# bb-psu-mk-1_0.net
KiCad netlist of a schematic drawn in EAGLE
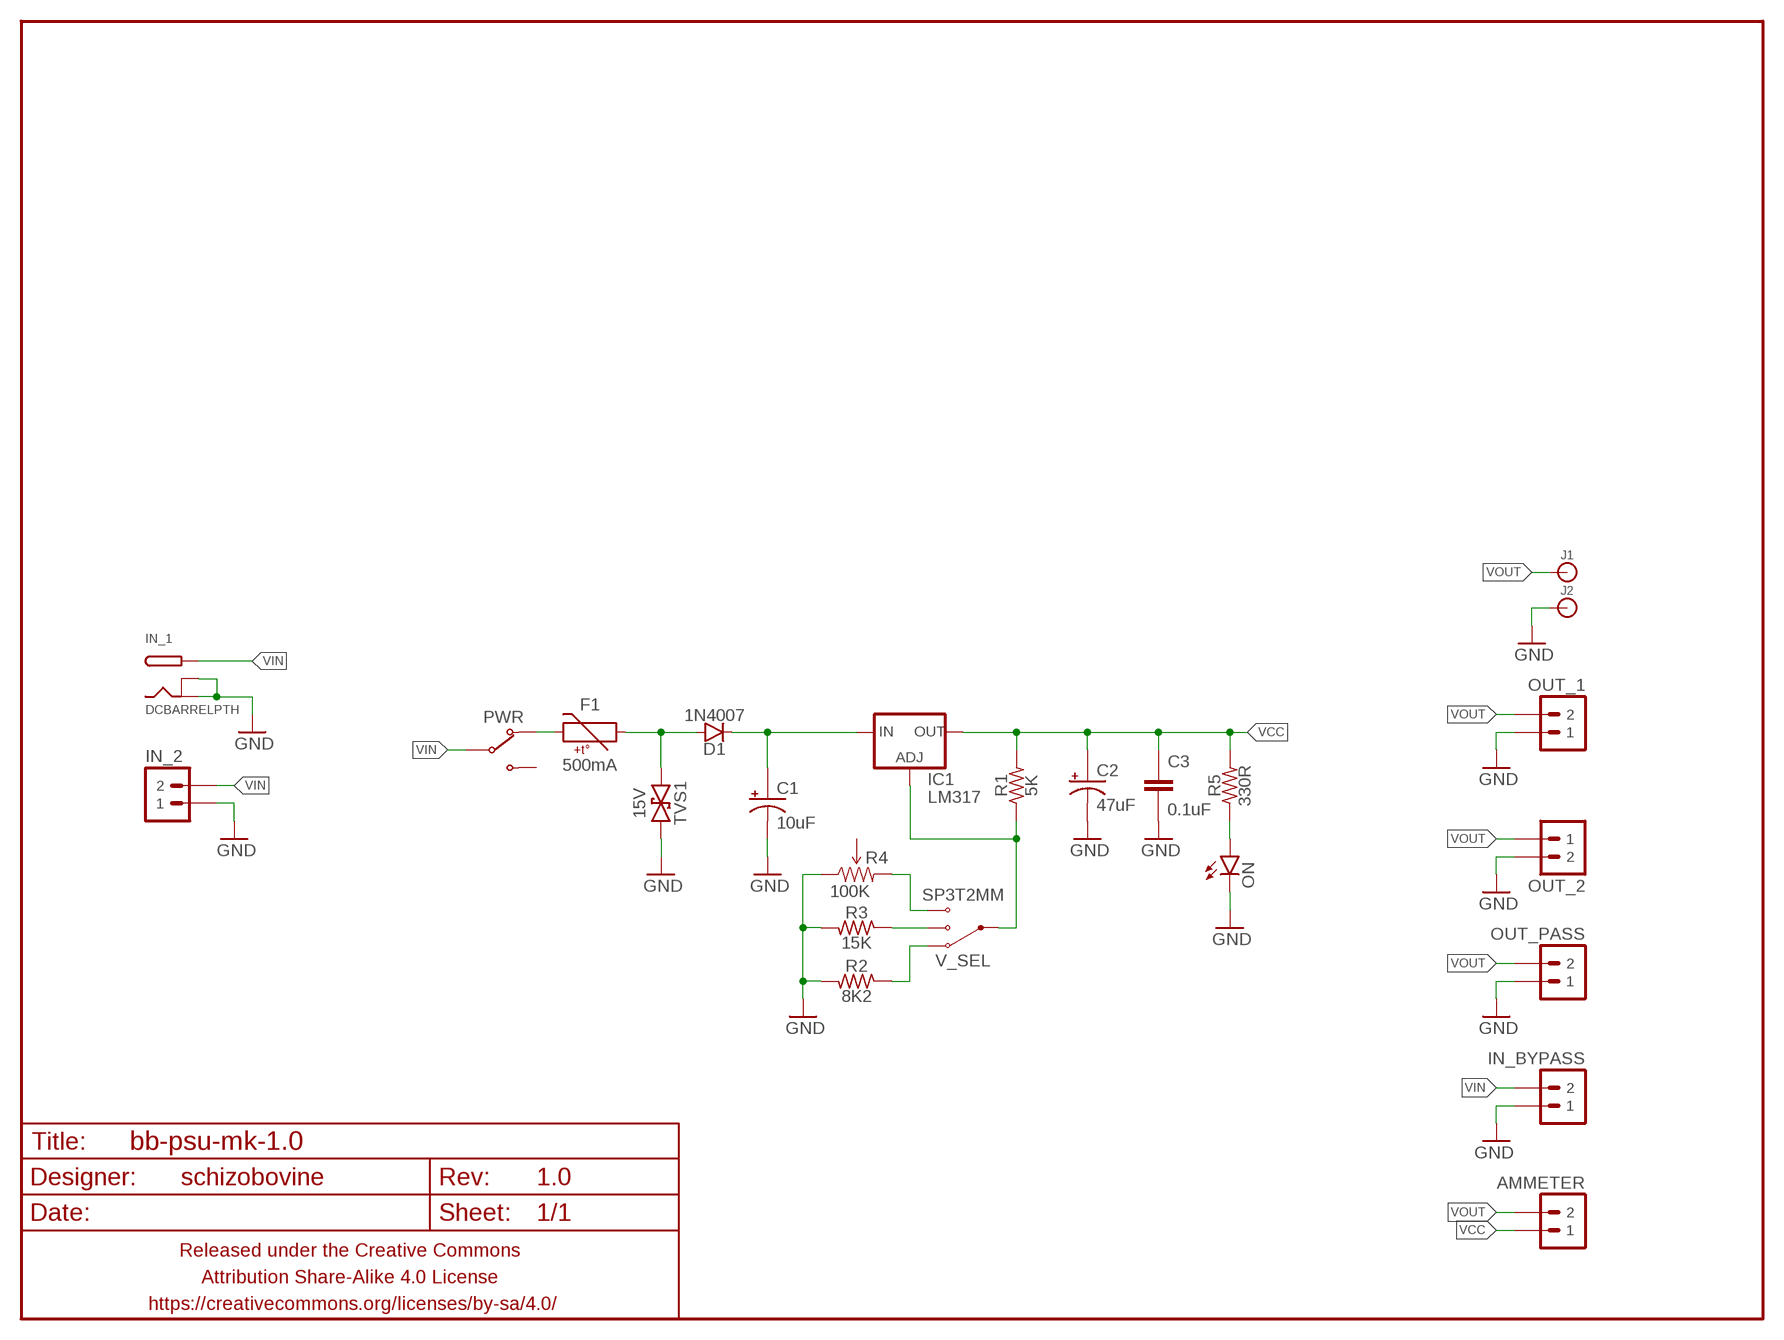
[diagram p0: schematic, sheet 1]

(export (version "E")
  (design (tool "Eeschema 10.0.6"))
  (components
    (comp (ref "AMMETER")
      (value "M02PTH-CENTERED")
      (footprint "eagle-import:1X02-CENTER")
      (libsource (lib "eagle-import") (part "M02PTH-CENTERED"))
    )
    (comp (ref "C1")
      (value "10uF")
      (footprint "eagle-import:E2,5-6")
      (libsource (lib "eagle-import") (part "CAPACITOR-POLARIZEDE2.5-6"))
    )
    (comp (ref "C2")
      (value "47uF")
      (footprint "eagle-import:E2,5-6")
      (libsource (lib "eagle-import") (part "CAPACITOR-POLARIZEDE2.5-6"))
    )
    (comp (ref "C3")
      (value "0.1uF")
      (footprint "eagle-import:C025-024X044")
      (libsource (lib "eagle-import") (part "CAPACITOR-CERAMIC025-024X044"))
    )
    (comp (ref "D1")
      (value "1N4007")
      (footprint "eagle-import:DIODE-10.16MM")
      (libsource (lib "eagle-import") (part "DIODEPTH-10.68MM"))
    )
    (comp (ref "F1")
      (value "500mA")
      (footprint "eagle-import:PTC-PTH-5.08MM")
      (libsource (lib "eagle-import") (part "PTCPTH-5.08MM"))
    )
    (comp (ref "FRAME1")
      (value "FRAME-LETTERNO_PACKAGE")
      (footprint "eagle-import:DUMMY")
      (fields (field (name "DESIGNER") "schizobovine") (field (name "VERSION") "1.0"))
      (libsource (lib "eagle-import") (part "FRAME-LETTERNO_PACKAGE"))
    )
    (comp (ref "IC1")
      (value "LM317")
      (footprint "eagle-import:TO220-THERMPAD")
      (libsource (lib "eagle-import") (part "V_REG_317THERMPAD"))
    )
    (comp (ref "IN_1")
      (value "DCBARRELPTH")
      (footprint "eagle-import:DCJACK_2MM_PTH")
      (libsource (lib "eagle-import") (part "DCBARRELPTH"))
    )
    (comp (ref "IN_2")
      (value "M02PTH-CENTERED-R+")
      (footprint "eagle-import:1X02-CENTER-R+")
      (libsource (lib "eagle-import") (part "M02PTH-CENTERED-R+"))
    )
    (comp (ref "IN_BYPASS")
      (value "M02PTH-CENTERED-R+")
      (footprint "eagle-import:1X02-CENTER-R+")
      (libsource (lib "eagle-import") (part "M02PTH-CENTERED-R+"))
    )
    (comp (ref "J1")
      (value "BANANA_CONNPOAST")
      (footprint "eagle-import:BINDING_POST")
      (libsource (lib "eagle-import") (part "BANANA_CONNPOAST"))
    )
    (comp (ref "J2")
      (value "BANANA_CONNPOAST")
      (footprint "eagle-import:BINDING_POST")
      (libsource (lib "eagle-import") (part "BANANA_CONNPOAST"))
    )
    (comp (ref "ON")
      (value "LED3MM-LESS")
      (footprint "eagle-import:LED3MM-LESSSILK")
      (libsource (lib "eagle-import") (part "LED3MM-LESS"))
    )
    (comp (ref "OUT_1")
      (value "M02PTH-CENTERED-R+")
      (footprint "eagle-import:1X02-CENTER-R+")
      (libsource (lib "eagle-import") (part "M02PTH-CENTERED-R+"))
    )
    (comp (ref "OUT_2")
      (value "M023.5MM")
      (footprint "eagle-import:SCREWTERMINAL-3.5MM-2")
      (libsource (lib "eagle-import") (part "M023.5MM"))
    )
    (comp (ref "OUT_PASS")
      (value "M02PTH-CENTERED-R+")
      (footprint "eagle-import:1X02-CENTER-R+")
      (libsource (lib "eagle-import") (part "M02PTH-CENTERED-R+"))
    )
    (comp (ref "PWR")
      (value "SWITCH-SPDTPTH-RA-2.54MM")
      (footprint "eagle-import:SPDT-RA-2.54MM")
      (libsource (lib "eagle-import") (part "SWITCH-SPDTPTH-RA-2.54MM"))
    )
    (comp (ref "R1")
      (value "5K")
      (footprint "eagle-import:RESISTOR-AXIAL-PTH-6.35MM")
      (libsource (lib "eagle-import") (part "RESISTORPTH-AXIAL-6.35MM"))
    )
    (comp (ref "R2")
      (value "8K2")
      (footprint "eagle-import:RESISTOR-AXIAL-PTH-6.35MM")
      (libsource (lib "eagle-import") (part "RESISTORPTH-AXIAL-6.35MM"))
    )
    (comp (ref "R3")
      (value "15K")
      (footprint "eagle-import:RESISTOR-AXIAL-PTH-6.35MM")
      (libsource (lib "eagle-import") (part "RESISTORPTH-AXIAL-6.35MM"))
    )
    (comp (ref "R4")
      (value "100K")
      (footprint "eagle-import:3386U")
      (libsource (lib "eagle-import") (part "TRIMPOT-PTH-KNOB"))
    )
    (comp (ref "R5")
      (value "330R")
      (footprint "eagle-import:RESISTOR-AXIAL-PTH-6.35MM")
      (libsource (lib "eagle-import") (part "RESISTORPTH-AXIAL-6.35MM"))
    )
    (comp (ref "TVS1")
      (value "15V")
      (footprint "eagle-import:DO-41-TVS-BI-10.16MM")
      (libsource (lib "eagle-import") (part "TVSDO-41-10.16MM"))
    )
    (comp (ref "V_SEL")
      (value "SP3T2MM")
      (footprint "eagle-import:SP3T-2MM")
      (libsource (lib "eagle-import") (part "SP3T2MM"))
    )
  )
  (nets
    (net (code "1") (name "GND") (class "Default")
      (node (ref "C1") (pin "-") (pinfunction "-_-") (pintype "passive"))
      (node (ref "C2") (pin "-") (pinfunction "-_-") (pintype "passive"))
      (node (ref "C3") (pin "2") (pinfunction "2_2") (pintype "passive"))
      (node (ref "IN_1") (pin "BRK") (pinfunction "BRK_BRK") (pintype "bidirectional"))
      (node (ref "IN_1") (pin "GND") (pinfunction "GND_GND") (pintype "bidirectional"))
      (node (ref "IN_2") (pin "1") (pinfunction "1_1") (pintype "passive"))
      (node (ref "IN_BYPASS") (pin "1") (pinfunction "1_1") (pintype "passive"))
      (node (ref "J2") (pin "P$1") (pinfunction "1_P$1") (pintype "passive"))
      (node (ref "ON") (pin "K") (pinfunction "C_K") (pintype "passive"))
      (node (ref "OUT_1") (pin "1") (pinfunction "1_1") (pintype "passive"))
      (node (ref "OUT_2") (pin "2") (pinfunction "2_2") (pintype "passive"))
      (node (ref "OUT_PASS") (pin "1") (pinfunction "1_1") (pintype "passive"))
      (node (ref "R2") (pin "P$2") (pinfunction "2_P$2") (pintype "passive"))
      (node (ref "R3") (pin "P$2") (pinfunction "2_P$2") (pintype "passive"))
      (node (ref "R4") (pin "1") (pinfunction "CCW_1") (pintype "passive"))
      (node (ref "TVS1") (pin "P$2") (pinfunction "2_P$2") (pintype "passive"))
    )
    (net (code "2") (name "Net-(F1-1)") (class "Default")
      (node (ref "D1") (pin "A") (pinfunction "A_A") (pintype "passive"))
      (node (ref "F1") (pin "P$1") (pinfunction "1_P$1") (pintype "passive"))
      (node (ref "TVS1") (pin "P$1") (pinfunction "1_P$1") (pintype "passive"))
    )
    (net (code "3") (name "Net-(F1-2)") (class "Default")
      (node (ref "F1") (pin "P$2") (pinfunction "2_P$2") (pintype "passive"))
      (node (ref "PWR") (pin "1") (pinfunction "NC_1") (pintype "passive"))
    )
    (net (code "4") (name "Net-(IC1-ADJ)") (class "Default")
      (node (ref "IC1") (pin "1") (pinfunction "ADJ_1") (pintype "input"))
      (node (ref "R1") (pin "P$1") (pinfunction "1_P$1") (pintype "passive"))
      (node (ref "V_SEL") (pin "P$1") (pinfunction "COM_P$1") (pintype "bidirectional"))
    )
    (net (code "5") (name "Net-(IC1-IN)") (class "Default")
      (node (ref "C1") (pin "+") (pinfunction "+_+") (pintype "passive"))
      (node (ref "D1") (pin "C") (pinfunction "C_C") (pintype "passive"))
      (node (ref "IC1") (pin "3") (pinfunction "IN_3") (pintype "input"))
    )
    (net (code "6") (name "Net-(R2-1)") (class "Default")
      (node (ref "R2") (pin "P$1") (pinfunction "1_P$1") (pintype "passive"))
      (node (ref "V_SEL") (pin "P$2") (pinfunction "A_P$2") (pintype "bidirectional"))
    )
    (net (code "7") (name "Net-(R3-1)") (class "Default")
      (node (ref "R3") (pin "P$1") (pinfunction "1_P$1") (pintype "passive"))
      (node (ref "V_SEL") (pin "P$3") (pinfunction "B_P$3") (pintype "bidirectional"))
    )
    (net (code "8") (name "Net-(R4-CW)") (class "Default")
      (node (ref "R4") (pin "3") (pinfunction "CW_3") (pintype "passive"))
      (node (ref "V_SEL") (pin "P$4") (pinfunction "C_P$4") (pintype "bidirectional"))
    )
    (net (code "9") (name "Net-(R5-1)") (class "Default")
      (node (ref "ON") (pin "A") (pinfunction "A_A") (pintype "passive"))
      (node (ref "R5") (pin "P$1") (pinfunction "1_P$1") (pintype "passive"))
    )
    (net (code "10") (name "VCC") (class "Default")
      (node (ref "AMMETER") (pin "1") (pinfunction "1_1") (pintype "passive"))
      (node (ref "C2") (pin "+") (pinfunction "+_+") (pintype "passive"))
      (node (ref "C3") (pin "1") (pinfunction "1_1") (pintype "passive"))
      (node (ref "IC1") (pin "2@1") (pinfunction "OUT_2@1") (pintype "output"))
      (node (ref "IC1") (pin "2@2") (pinfunction "OUT_2@2") (pintype "output"))
      (node (ref "R1") (pin "P$2") (pinfunction "2_P$2") (pintype "passive"))
      (node (ref "R5") (pin "P$2") (pinfunction "2_P$2") (pintype "passive"))
    )
    (net (code "11") (name "VIN") (class "Default")
      (node (ref "IN_1") (pin "PWR") (pinfunction "PWR_PWR") (pintype "bidirectional"))
      (node (ref "IN_2") (pin "2") (pinfunction "2_2") (pintype "passive"))
      (node (ref "IN_BYPASS") (pin "2") (pinfunction "2_2") (pintype "passive"))
      (node (ref "PWR") (pin "2") (pinfunction "COM_2") (pintype "passive"))
    )
    (net (code "12") (name "VOUT") (class "Default")
      (node (ref "AMMETER") (pin "2") (pinfunction "2_2") (pintype "passive"))
      (node (ref "J1") (pin "P$1") (pinfunction "1_P$1") (pintype "passive"))
      (node (ref "OUT_1") (pin "2") (pinfunction "2_2") (pintype "passive"))
      (node (ref "OUT_2") (pin "1") (pinfunction "1_1") (pintype "passive"))
      (node (ref "OUT_PASS") (pin "2") (pinfunction "2_2") (pintype "passive"))
    )
    (net (code "13") (name "unconnected-(PWR-NO-Pad3)") (class "Default")
      (node (ref "PWR") (pin "3") (pinfunction "NO_3") (pintype "passive"))
    )
    (net (code "14") (name "unconnected-(R4-WIPER-Pad2)") (class "Default")
      (node (ref "R4") (pin "2") (pinfunction "WIPER_2") (pintype "passive"))
    )
  )
)
